# f_log_rind.net
KiCad netlist of a schematic drawn in EAGLE
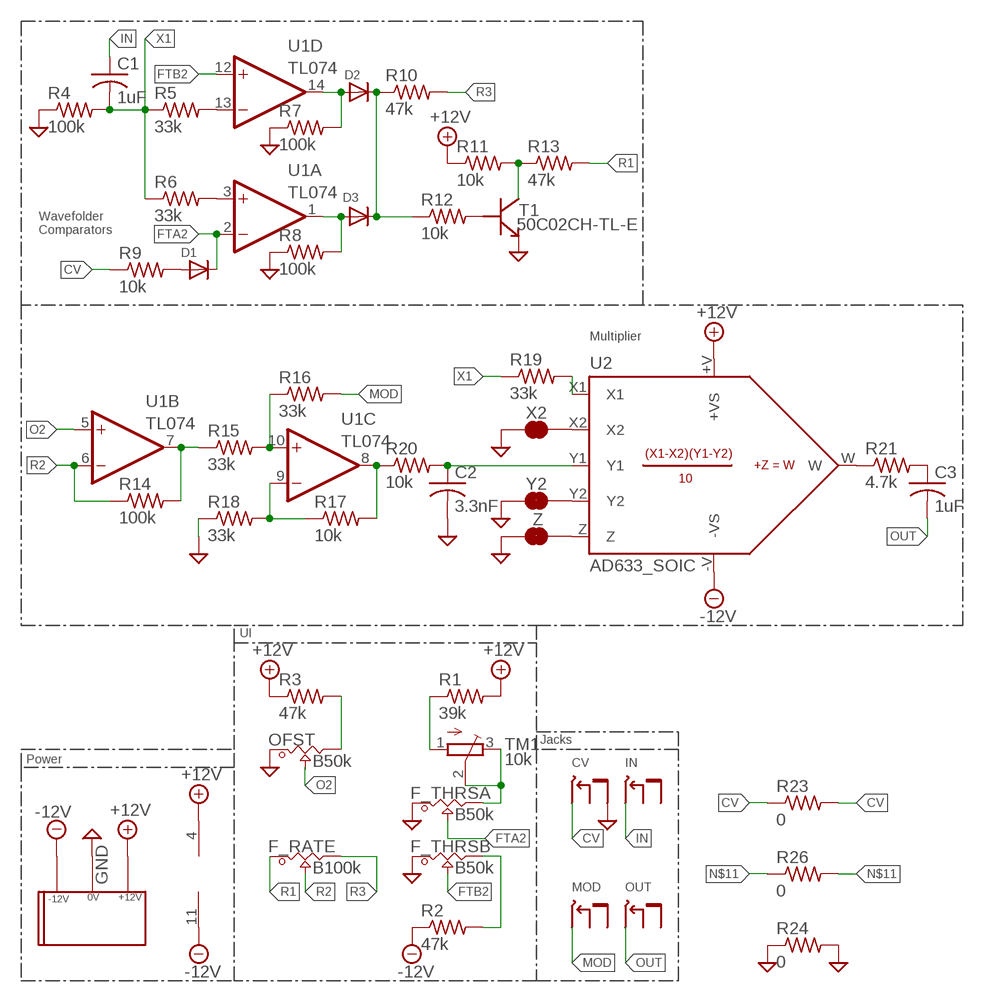
[diagram p0: schematic, sheet 1]

(export (version "E")
  (design (tool "Eeschema 10.0.6"))
  (components
    (comp (ref "C1")
      (value "1uF")
      (footprint "eagle-import:C0603")
      (libsource (lib "eagle-import") (part "C-USC0603"))
    )
    (comp (ref "C2")
      (value "3.3nF")
      (footprint "eagle-import:C0603")
      (libsource (lib "eagle-import") (part "C-USC0603"))
    )
    (comp (ref "C3")
      (value "1uF")
      (footprint "eagle-import:C0603")
      (libsource (lib "eagle-import") (part "C-USC0603"))
    )
    (comp (ref "D1")
      (value "DIODESOD-123")
      (footprint "eagle-import:SOD-123")
      (libsource (lib "eagle-import") (part "DIODESOD-123"))
    )
    (comp (ref "D2")
      (value "DIODESOD-123")
      (footprint "eagle-import:SOD-123")
      (libsource (lib "eagle-import") (part "DIODESOD-123"))
    )
    (comp (ref "D3")
      (value "DIODESOD-123")
      (footprint "eagle-import:SOD-123")
      (libsource (lib "eagle-import") (part "DIODESOD-123"))
    )
    (comp (ref "F_RATE")
      (value "B100k")
      (footprint "eagle-import:POT_9MM_SMD")
      (libsource (lib "eagle-import") (part "POT_9MM_SMD"))
    )
    (comp (ref "F_THRSA")
      (value "B50k")
      (footprint "eagle-import:POT_9MM_SMD")
      (libsource (lib "eagle-import") (part "POT_9MM_SMD"))
    )
    (comp (ref "F_THRSB")
      (value "B50k")
      (footprint "eagle-import:POT_9MM_SMD")
      (libsource (lib "eagle-import") (part "POT_9MM_SMD"))
    )
    (comp (ref "J_A1")
      (value "THONKICONN_CE_4X_COMG_NOSW")
      (footprint "eagle-import:1.27MM_CE_4X_COMG_NOSW")
      (libsource (lib "eagle-import") (part "THONKICONN_CE_4X_COMG_NOSW"))
    )
    (comp (ref "OFST")
      (value "B50k")
      (footprint "eagle-import:POT_9MM_SMD")
      (libsource (lib "eagle-import") (part "POT_9MM_SMD"))
    )
    (comp (ref "R1")
      (value "39k")
      (footprint "eagle-import:R0603")
      (libsource (lib "eagle-import") (part "R-US_R0603"))
    )
    (comp (ref "R2")
      (value "47k")
      (footprint "eagle-import:R0603")
      (libsource (lib "eagle-import") (part "R-US_R0603"))
    )
    (comp (ref "R3")
      (value "47k")
      (footprint "eagle-import:R0603")
      (libsource (lib "eagle-import") (part "R-US_R0603"))
    )
    (comp (ref "R4")
      (value "100k")
      (footprint "eagle-import:R0603")
      (libsource (lib "eagle-import") (part "R-US_R0603"))
    )
    (comp (ref "R5")
      (value "33k")
      (footprint "eagle-import:R0603")
      (libsource (lib "eagle-import") (part "R-US_R0603"))
    )
    (comp (ref "R6")
      (value "33k")
      (footprint "eagle-import:R0603")
      (libsource (lib "eagle-import") (part "R-US_R0603"))
    )
    (comp (ref "R7")
      (value "100k")
      (footprint "eagle-import:R0603")
      (libsource (lib "eagle-import") (part "R-US_R0603"))
    )
    (comp (ref "R8")
      (value "100k")
      (footprint "eagle-import:R0603")
      (libsource (lib "eagle-import") (part "R-US_R0603"))
    )
    (comp (ref "R9")
      (value "10k")
      (footprint "eagle-import:R0603")
      (libsource (lib "eagle-import") (part "R-US_R0603"))
    )
    (comp (ref "R10")
      (value "47k")
      (footprint "eagle-import:R0603")
      (libsource (lib "eagle-import") (part "R-US_R0603"))
    )
    (comp (ref "R11")
      (value "10k")
      (footprint "eagle-import:R0603")
      (libsource (lib "eagle-import") (part "R-US_R0603"))
    )
    (comp (ref "R12")
      (value "10k")
      (footprint "eagle-import:R0603")
      (libsource (lib "eagle-import") (part "R-US_R0603"))
    )
    (comp (ref "R13")
      (value "47k")
      (footprint "eagle-import:R0603")
      (libsource (lib "eagle-import") (part "R-US_R0603"))
    )
    (comp (ref "R14")
      (value "100k")
      (footprint "eagle-import:R0603")
      (libsource (lib "eagle-import") (part "R-US_R0603"))
    )
    (comp (ref "R15")
      (value "33k")
      (footprint "eagle-import:R0603")
      (libsource (lib "eagle-import") (part "R-US_R0603"))
    )
    (comp (ref "R16")
      (value "33k")
      (footprint "eagle-import:R0603")
      (libsource (lib "eagle-import") (part "R-US_R0603"))
    )
    (comp (ref "R17")
      (value "10k")
      (footprint "eagle-import:R0603")
      (libsource (lib "eagle-import") (part "R-US_R0603"))
    )
    (comp (ref "R18")
      (value "33k")
      (footprint "eagle-import:R0603")
      (libsource (lib "eagle-import") (part "R-US_R0603"))
    )
    (comp (ref "R19")
      (value "33k")
      (footprint "eagle-import:R0603")
      (libsource (lib "eagle-import") (part "R-US_R0603"))
    )
    (comp (ref "R20")
      (value "10k")
      (footprint "eagle-import:R0603")
      (libsource (lib "eagle-import") (part "R-US_R0603"))
    )
    (comp (ref "R21")
      (value "4.7k")
      (footprint "eagle-import:R0603")
      (libsource (lib "eagle-import") (part "R-US_R0603"))
    )
    (comp (ref "R23")
      (value "0")
      (footprint "eagle-import:R0402")
      (libsource (lib "eagle-import") (part "R-US_R0402"))
    )
    (comp (ref "R24")
      (value "0")
      (footprint "eagle-import:R0402")
      (libsource (lib "eagle-import") (part "R-US_R0402"))
    )
    (comp (ref "R26")
      (value "0")
      (footprint "eagle-import:R0402")
      (libsource (lib "eagle-import") (part "R-US_R0402"))
    )
    (comp (ref "T1")
      (value "50C02CH-TL-E")
      (footprint "eagle-import:BEC")
      (libsource (lib "eagle-import") (part "50C02CH-TL-E"))
    )
    (comp (ref "TM1")
      (value "10k")
      (footprint "eagle-import:TC33X")
      (libsource (lib "eagle-import") (part "TRIMPOTTC33X"))
    )
    (comp (ref "U$1")
      (value "EURO_POW_CEH")
      (footprint "eagle-import:EURO_POW_CEH")
      (libsource (lib "eagle-import") (part "EURO_POW_CEH"))
    )
    (comp (ref "U1")
      (value "TL074")
      (footprint "eagle-import:SO14")
      (libsource (lib "eagle-import") (part "TL074_SMD"))
    )
    (comp (ref "U2")
      (value "AD633_SOIC")
      (footprint "eagle-import:SOIC_8")
      (libsource (lib "eagle-import") (part "AD633_SOIC"))
    )
    (comp (ref "X2")
      (value "JUMPER-SMT_2_NC_TRACE_NO-SILK")
      (footprint "eagle-import:SMT-JUMPER_2_NC_TRACE_NO-SILK")
      (libsource (lib "eagle-import") (part "JUMPER-SMT_2_NC_TRACE_NO-SILK"))
    )
    (comp (ref "Y2")
      (value "JUMPER-SMT_2_NC_TRACE_NO-SILK")
      (footprint "eagle-import:SMT-JUMPER_2_NC_TRACE_NO-SILK")
      (libsource (lib "eagle-import") (part "JUMPER-SMT_2_NC_TRACE_NO-SILK"))
    )
    (comp (ref "Z")
      (value "JUMPER-SMT_2_NC_TRACE_NO-SILK")
      (footprint "eagle-import:SMT-JUMPER_2_NC_TRACE_NO-SILK")
      (libsource (lib "eagle-import") (part "JUMPER-SMT_2_NC_TRACE_NO-SILK"))
    )
  )
  (nets
    (net (code "1") (name "+12V") (class "Default")
      (node (ref "R1") (pin "2") (pinfunction "2_2") (pintype "passive"))
      (node (ref "R11") (pin "1") (pinfunction "1_1") (pintype "passive"))
      (node (ref "R3") (pin "1") (pinfunction "1_1") (pintype "passive"))
      (node (ref "U$1") (pin "+12V") (pinfunction "+12V_+12V") (pintype "bidirectional"))
      (node (ref "U1") (pin "4") (pinfunction "V+_4") (pintype "power_in"))
      (node (ref "U2") (pin "+V") (pinfunction "+VS_+V") (pintype "power_in"))
    )
    (net (code "2") (name "-12V") (class "Default")
      (node (ref "R2") (pin "1") (pinfunction "1_1") (pintype "passive"))
      (node (ref "U$1") (pin "-12V") (pinfunction "-12V_-12V") (pintype "bidirectional"))
      (node (ref "U1") (pin "11") (pinfunction "V-_11") (pintype "power_in"))
      (node (ref "U2") (pin "-V") (pinfunction "-VS_-V") (pintype "power_in"))
    )
    (net (code "3") (name "CV") (class "Default")
      (node (ref "J_A1") (pin "1") (pinfunction "T_1") (pintype "bidirectional"))
      (node (ref "R23") (pin "1") (pinfunction "1_1") (pintype "passive"))
      (node (ref "R23") (pin "2") (pinfunction "2_2") (pintype "passive"))
      (node (ref "R9") (pin "1") (pinfunction "1_1") (pintype "passive"))
    )
    (net (code "4") (name "FTA2") (class "Default")
      (node (ref "D1") (pin "C") (pinfunction "C_C") (pintype "passive"))
      (node (ref "F_THRSA") (pin "2") (pinfunction "2_2") (pintype "bidirectional"))
      (node (ref "U1") (pin "2") (pinfunction "-IN_2") (pintype "input"))
    )
    (net (code "5") (name "FTB2") (class "Default")
      (node (ref "F_THRSB") (pin "2") (pinfunction "2_2") (pintype "bidirectional"))
      (node (ref "U1") (pin "12") (pinfunction "+IN_12") (pintype "input"))
    )
    (net (code "6") (name "GND") (class "Default")
      (node (ref "C2") (pin "2") (pinfunction "2_2") (pintype "passive"))
      (node (ref "F_THRSA") (pin "1") (pinfunction "1_1") (pintype "bidirectional"))
      (node (ref "F_THRSB") (pin "1") (pinfunction "1_1") (pintype "bidirectional"))
      (node (ref "J_A1") (pin "0") (pinfunction "S_0") (pintype "bidirectional"))
      (node (ref "OFST") (pin "1") (pinfunction "1_1") (pintype "bidirectional"))
      (node (ref "R18") (pin "1") (pinfunction "1_1") (pintype "passive"))
      (node (ref "R24") (pin "1") (pinfunction "1_1") (pintype "passive"))
      (node (ref "R24") (pin "2") (pinfunction "2_2") (pintype "passive"))
      (node (ref "R4") (pin "1") (pinfunction "1_1") (pintype "passive"))
      (node (ref "R7") (pin "1") (pinfunction "1_1") (pintype "passive"))
      (node (ref "R8") (pin "1") (pinfunction "1_1") (pintype "passive"))
      (node (ref "T1") (pin "E") (pinfunction "E_E") (pintype "bidirectional"))
      (node (ref "U$1") (pin "GND") (pinfunction "GND_GND") (pintype "bidirectional"))
      (node (ref "X2") (pin "1") (pinfunction "1_1") (pintype "passive"))
      (node (ref "Y2") (pin "1") (pinfunction "1_1") (pintype "passive"))
      (node (ref "Z") (pin "1") (pinfunction "1_1") (pintype "passive"))
    )
    (net (code "7") (name "IN") (class "Default")
      (node (ref "C1") (pin "1") (pinfunction "1_1") (pintype "passive"))
      (node (ref "J_A1") (pin "2") (pinfunction "T_2") (pintype "bidirectional"))
    )
    (net (code "8") (name "MOD") (class "Default")
      (node (ref "J_A1") (pin "3") (pinfunction "T_3") (pintype "bidirectional"))
      (node (ref "R16") (pin "2") (pinfunction "2_2") (pintype "passive"))
    )
    (net (code "9") (name "N$11") (class "Default")
      (node (ref "D2") (pin "C") (pinfunction "C_C") (pintype "passive"))
      (node (ref "D3") (pin "C") (pinfunction "C_C") (pintype "passive"))
      (node (ref "R10") (pin "1") (pinfunction "1_1") (pintype "passive"))
      (node (ref "R12") (pin "1") (pinfunction "1_1") (pintype "passive"))
      (node (ref "R26") (pin "1") (pinfunction "1_1") (pintype "passive"))
      (node (ref "R26") (pin "2") (pinfunction "2_2") (pintype "passive"))
    )
    (net (code "10") (name "Net-(C2-Pad1)") (class "Default")
      (node (ref "C2") (pin "1") (pinfunction "1_1") (pintype "passive"))
      (node (ref "R20") (pin "2") (pinfunction "2_2") (pintype "passive"))
      (node (ref "U2") (pin "Y1") (pinfunction "Y1_Y1") (pintype "input"))
    )
    (net (code "11") (name "Net-(C3-Pad1)") (class "Default")
      (node (ref "C3") (pin "1") (pinfunction "1_1") (pintype "passive"))
      (node (ref "R21") (pin "2") (pinfunction "2_2") (pintype "passive"))
    )
    (net (code "12") (name "Net-(D1-PadA)") (class "Default")
      (node (ref "D1") (pin "A") (pinfunction "A_A") (pintype "passive"))
      (node (ref "R9") (pin "2") (pinfunction "2_2") (pintype "passive"))
    )
    (net (code "13") (name "Net-(F_THRSB-Pad3)") (class "Default")
      (node (ref "F_THRSB") (pin "3") (pinfunction "3_3") (pintype "bidirectional"))
      (node (ref "R2") (pin "2") (pinfunction "2_2") (pintype "passive"))
    )
    (net (code "14") (name "Net-(OFST-Pad3)") (class "Default")
      (node (ref "OFST") (pin "3") (pinfunction "3_3") (pintype "bidirectional"))
      (node (ref "R3") (pin "2") (pinfunction "2_2") (pintype "passive"))
    )
    (net (code "15") (name "Net-(R11-Pad2)") (class "Default")
      (node (ref "R11") (pin "2") (pinfunction "2_2") (pintype "passive"))
      (node (ref "R13") (pin "1") (pinfunction "1_1") (pintype "passive"))
      (node (ref "T1") (pin "C") (pinfunction "C_C") (pintype "bidirectional"))
    )
    (net (code "16") (name "Net-(R12-Pad2)") (class "Default")
      (node (ref "R12") (pin "2") (pinfunction "2_2") (pintype "passive"))
      (node (ref "T1") (pin "B") (pinfunction "B_B") (pintype "bidirectional"))
    )
    (net (code "17") (name "Net-(R19-Pad2)") (class "Default")
      (node (ref "R19") (pin "2") (pinfunction "2_2") (pintype "passive"))
      (node (ref "U2") (pin "X1") (pinfunction "X1_X1") (pintype "input"))
    )
    (net (code "18") (name "Net-(R21-Pad1)") (class "Default")
      (node (ref "R21") (pin "1") (pinfunction "1_1") (pintype "passive"))
      (node (ref "U2") (pin "W") (pinfunction "W_W") (pintype "output"))
    )
    (net (code "19") (name "Net-(TM1-A)") (class "Default")
      (node (ref "R1") (pin "1") (pinfunction "1_1") (pintype "passive"))
      (node (ref "TM1") (pin "1") (pinfunction "A_1") (pintype "passive"))
    )
    (net (code "20") (name "Net-(TM1-E)") (class "Default")
      (node (ref "F_THRSA") (pin "3") (pinfunction "3_3") (pintype "bidirectional"))
      (node (ref "TM1") (pin "2") (pinfunction "S_2") (pintype "passive"))
      (node (ref "TM1") (pin "3") (pinfunction "E_3") (pintype "passive"))
    )
    (net (code "21") (name "Net-(U1A-+IN)") (class "Default")
      (node (ref "R6") (pin "2") (pinfunction "2_2") (pintype "passive"))
      (node (ref "U1") (pin "3") (pinfunction "+IN_3") (pintype "input"))
    )
    (net (code "22") (name "Net-(U1A-OUT)") (class "Default")
      (node (ref "D3") (pin "A") (pinfunction "A_A") (pintype "passive"))
      (node (ref "R8") (pin "2") (pinfunction "2_2") (pintype "passive"))
      (node (ref "U1") (pin "1") (pinfunction "OUT_1") (pintype "output"))
    )
    (net (code "23") (name "Net-(U1B-OUT)") (class "Default")
      (node (ref "R14") (pin "2") (pinfunction "2_2") (pintype "passive"))
      (node (ref "R15") (pin "1") (pinfunction "1_1") (pintype "passive"))
      (node (ref "U1") (pin "7") (pinfunction "OUT_7") (pintype "output"))
    )
    (net (code "24") (name "Net-(U1C-+IN)") (class "Default")
      (node (ref "R15") (pin "2") (pinfunction "2_2") (pintype "passive"))
      (node (ref "R16") (pin "1") (pinfunction "1_1") (pintype "passive"))
      (node (ref "U1") (pin "10") (pinfunction "+IN_10") (pintype "input"))
    )
    (net (code "25") (name "Net-(U1C--IN)") (class "Default")
      (node (ref "R17") (pin "1") (pinfunction "1_1") (pintype "passive"))
      (node (ref "R18") (pin "2") (pinfunction "2_2") (pintype "passive"))
      (node (ref "U1") (pin "9") (pinfunction "-IN_9") (pintype "input"))
    )
    (net (code "26") (name "Net-(U1C-OUT)") (class "Default")
      (node (ref "R17") (pin "2") (pinfunction "2_2") (pintype "passive"))
      (node (ref "R20") (pin "1") (pinfunction "1_1") (pintype "passive"))
      (node (ref "U1") (pin "8") (pinfunction "OUT_8") (pintype "output"))
    )
    (net (code "27") (name "Net-(U1D--IN)") (class "Default")
      (node (ref "R5") (pin "2") (pinfunction "2_2") (pintype "passive"))
      (node (ref "U1") (pin "13") (pinfunction "-IN_13") (pintype "input"))
    )
    (net (code "28") (name "Net-(U1D-OUT)") (class "Default")
      (node (ref "D2") (pin "A") (pinfunction "A_A") (pintype "passive"))
      (node (ref "R7") (pin "2") (pinfunction "2_2") (pintype "passive"))
      (node (ref "U1") (pin "14") (pinfunction "OUT_14") (pintype "output"))
    )
    (net (code "29") (name "Net-(U2-PadX2)") (class "Default")
      (node (ref "U2") (pin "X2") (pinfunction "X2_X2") (pintype "input"))
      (node (ref "X2") (pin "2") (pinfunction "2_2") (pintype "passive"))
    )
    (net (code "30") (name "Net-(U2-PadY2)") (class "Default")
      (node (ref "U2") (pin "Y2") (pinfunction "Y2_Y2") (pintype "input"))
      (node (ref "Y2") (pin "2") (pinfunction "2_2") (pintype "passive"))
    )
    (net (code "31") (name "Net-(U2-PadZ)") (class "Default")
      (node (ref "U2") (pin "Z") (pinfunction "Z_Z") (pintype "input"))
      (node (ref "Z") (pin "2") (pinfunction "2_2") (pintype "passive"))
    )
    (net (code "32") (name "O2") (class "Default")
      (node (ref "OFST") (pin "2") (pinfunction "2_2") (pintype "bidirectional"))
      (node (ref "U1") (pin "5") (pinfunction "+IN_5") (pintype "input"))
    )
    (net (code "33") (name "OUT") (class "Default")
      (node (ref "C3") (pin "2") (pinfunction "2_2") (pintype "passive"))
      (node (ref "J_A1") (pin "4") (pinfunction "T_4") (pintype "bidirectional"))
    )
    (net (code "34") (name "R1") (class "Default")
      (node (ref "F_RATE") (pin "1") (pinfunction "1_1") (pintype "bidirectional"))
      (node (ref "R13") (pin "2") (pinfunction "2_2") (pintype "passive"))
    )
    (net (code "35") (name "R2") (class "Default")
      (node (ref "F_RATE") (pin "2") (pinfunction "2_2") (pintype "bidirectional"))
      (node (ref "R14") (pin "1") (pinfunction "1_1") (pintype "passive"))
      (node (ref "U1") (pin "6") (pinfunction "-IN_6") (pintype "input"))
    )
    (net (code "36") (name "R3") (class "Default")
      (node (ref "F_RATE") (pin "3") (pinfunction "3_3") (pintype "bidirectional"))
      (node (ref "R10") (pin "2") (pinfunction "2_2") (pintype "passive"))
    )
    (net (code "37") (name "X1") (class "Default")
      (node (ref "C1") (pin "2") (pinfunction "2_2") (pintype "passive"))
      (node (ref "R19") (pin "1") (pinfunction "1_1") (pintype "passive"))
      (node (ref "R4") (pin "2") (pinfunction "2_2") (pintype "passive"))
      (node (ref "R5") (pin "1") (pinfunction "1_1") (pintype "passive"))
      (node (ref "R6") (pin "1") (pinfunction "1_1") (pintype "passive"))
    )
  )
)
